# ADC_Board_TOP.net
KiCad netlist of a schematic drawn in Altium Designer
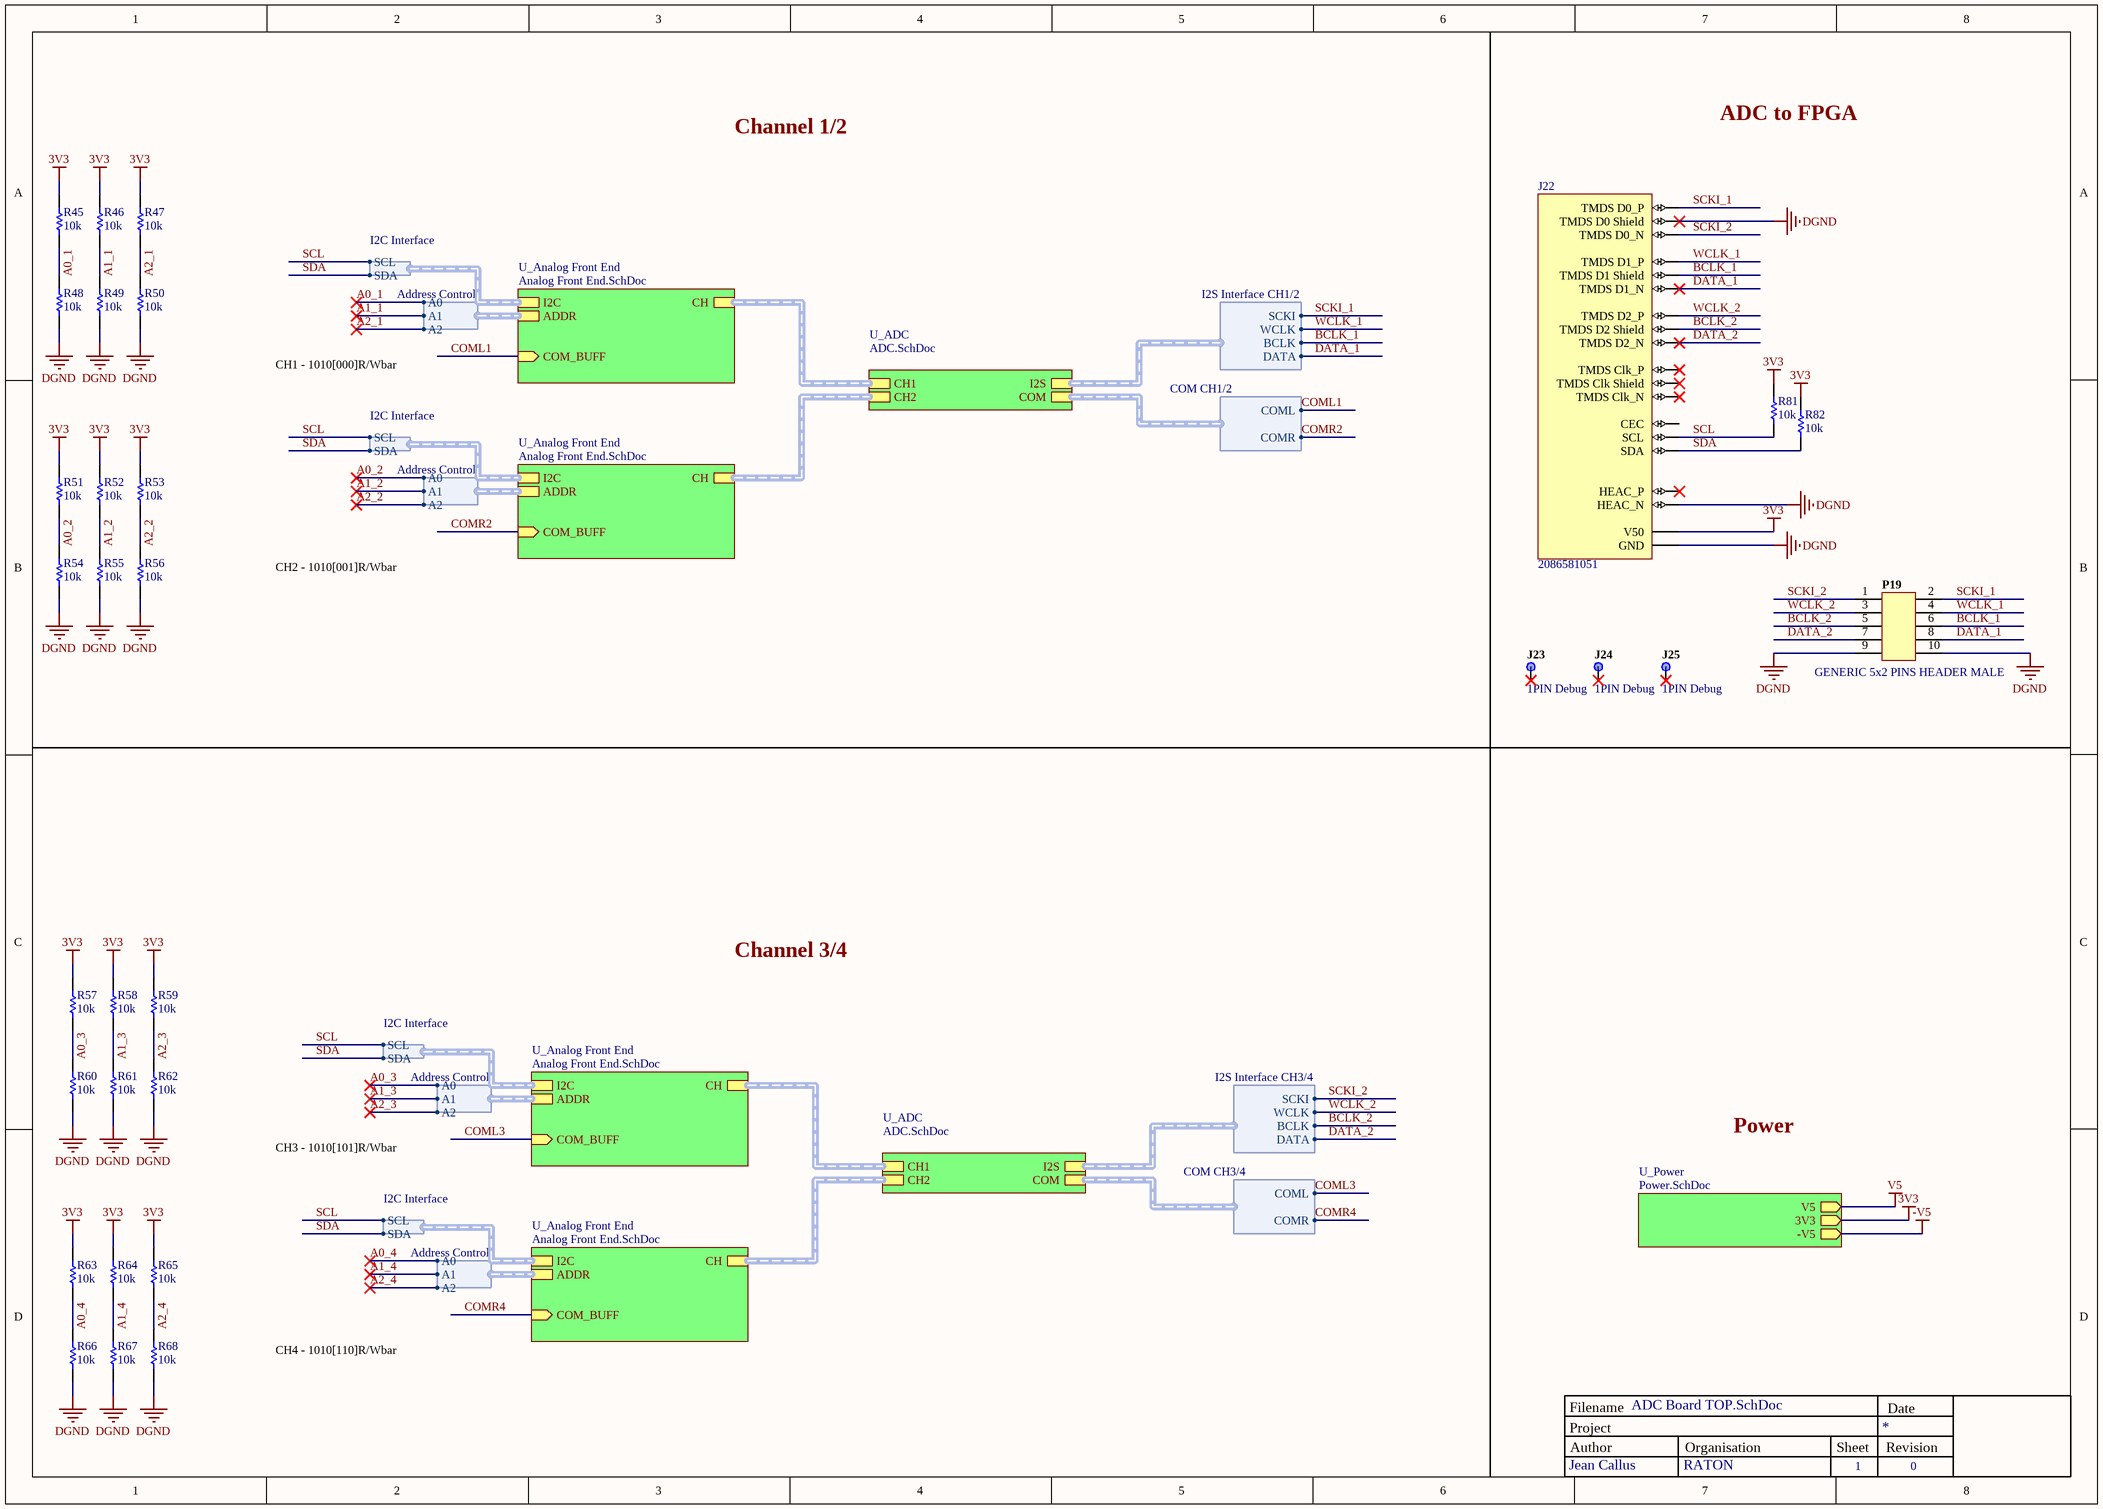
[diagram p0: ADC Board TOP.SchDoc]

(export (version "E")
  (design (tool "Eeschema 10.0.6"))
  (components
    (comp (ref "J22")
      (value "2086581051")
      (footprint "2086581051")
      (description "CONN FEM SMD 19 90Deg HDMI")
      (fields (field (name "DESIGN ITEM ID") "2086581051") (field (name "MANUFACTURER") "Molex"))
      (libsource (lib "") (part "Symbol_1"))
    )
    (comp (ref "J23")
      (value "1PIN Debug")
      (footprint "1 Pin Debug Port 0.9mm")
      (description "CONN MAL TH 1 0Deg HEADER")
      (fields (field (name "DESIGN ITEM ID") "1PIN Debug"))
      (libsource (lib "University of Malta - MEMENTO") (part "1PIN Debug"))
    )
    (comp (ref "J24")
      (value "1PIN Debug")
      (footprint "1 Pin Debug Port 0.9mm")
      (description "CONN MAL TH 1 0Deg HEADER")
      (fields (field (name "DESIGN ITEM ID") "1PIN Debug"))
      (libsource (lib "University of Malta - MEMENTO") (part "1PIN Debug"))
    )
    (comp (ref "J25")
      (value "1PIN Debug")
      (footprint "1 Pin Debug Port 0.9mm")
      (description "CONN MAL TH 1 0Deg HEADER")
      (fields (field (name "DESIGN ITEM ID") "1PIN Debug"))
      (libsource (lib "University of Malta - MEMENTO") (part "1PIN Debug"))
    )
    (comp (ref "P19")
      (value "GENERIC 5x2 PINS HEADER MALE")
      (footprint "GENERIC 5PIN 2ROW HEADER 0")
      (description "CONN MAL TH 5x2 0Deg HEADER")
      (fields
        (field (name "DESIGN ITEM ID") "GENERIC 5x2 PINS HEADER MALE")
        (field (name "MANUFACTURER") "Generic")
      )
      (libsource (lib "University of Malta - MEMENTO") (part "GENERIC 5x2 PINS HEADER MALE"))
    )
    (comp (ref "R45")
      (value "10k")
      (footprint "0402-M")
      (description "RES-10k-0402-63mW-5%")
      (fields (field (name "MANUFACTURER") "Generic") (field (name "Comment") "RES 10k 0402 63mW 5%"))
      (libsource (lib "University of Malta - MEMENTO") (part "Symbol"))
    )
    (comp (ref "R46")
      (value "10k")
      (footprint "0402-M")
      (description "RES-10k-0402-63mW-5%")
      (fields (field (name "MANUFACTURER") "Generic") (field (name "Comment") "RES 10k 0402 63mW 5%"))
      (libsource (lib "University of Malta - MEMENTO") (part "Symbol"))
    )
    (comp (ref "R47")
      (value "10k")
      (footprint "0402-M")
      (description "RES-10k-0402-63mW-5%")
      (fields (field (name "MANUFACTURER") "Generic") (field (name "Comment") "RES 10k 0402 63mW 5%"))
      (libsource (lib "University of Malta - MEMENTO") (part "Symbol"))
    )
    (comp (ref "R48")
      (value "10k")
      (footprint "0402-M")
      (description "RES-10k-0402-63mW-5%")
      (fields (field (name "MANUFACTURER") "Generic") (field (name "Comment") "RES 10k 0402 63mW 5%"))
      (libsource (lib "University of Malta - MEMENTO") (part "Symbol"))
    )
    (comp (ref "R49")
      (value "10k")
      (footprint "0402-M")
      (description "RES-10k-0402-63mW-5%")
      (fields (field (name "MANUFACTURER") "Generic") (field (name "Comment") "RES 10k 0402 63mW 5%"))
      (libsource (lib "University of Malta - MEMENTO") (part "Symbol"))
    )
    (comp (ref "R50")
      (value "10k")
      (footprint "0402-M")
      (description "RES-10k-0402-63mW-5%")
      (fields (field (name "MANUFACTURER") "Generic") (field (name "Comment") "RES 10k 0402 63mW 5%"))
      (libsource (lib "University of Malta - MEMENTO") (part "Symbol"))
    )
    (comp (ref "R51")
      (value "10k")
      (footprint "0402-M")
      (description "RES-10k-0402-63mW-5%")
      (fields (field (name "MANUFACTURER") "Generic") (field (name "Comment") "RES 10k 0402 63mW 5%"))
      (libsource (lib "University of Malta - MEMENTO") (part "Symbol"))
    )
    (comp (ref "R52")
      (value "10k")
      (footprint "0402-M")
      (description "RES-10k-0402-63mW-5%")
      (fields (field (name "MANUFACTURER") "Generic") (field (name "Comment") "RES 10k 0402 63mW 5%"))
      (libsource (lib "University of Malta - MEMENTO") (part "Symbol"))
    )
    (comp (ref "R53")
      (value "10k")
      (footprint "0402-M")
      (description "RES-10k-0402-63mW-5%")
      (fields (field (name "MANUFACTURER") "Generic") (field (name "Comment") "RES 10k 0402 63mW 5%"))
      (libsource (lib "University of Malta - MEMENTO") (part "Symbol"))
    )
    (comp (ref "R54")
      (value "10k")
      (footprint "0402-M")
      (description "RES-10k-0402-63mW-5%")
      (fields (field (name "MANUFACTURER") "Generic") (field (name "Comment") "RES 10k 0402 63mW 5%"))
      (libsource (lib "University of Malta - MEMENTO") (part "Symbol"))
    )
    (comp (ref "R55")
      (value "10k")
      (footprint "0402-M")
      (description "RES-10k-0402-63mW-5%")
      (fields (field (name "MANUFACTURER") "Generic") (field (name "Comment") "RES 10k 0402 63mW 5%"))
      (libsource (lib "University of Malta - MEMENTO") (part "Symbol"))
    )
    (comp (ref "R56")
      (value "10k")
      (footprint "0402-M")
      (description "RES-10k-0402-63mW-5%")
      (fields (field (name "MANUFACTURER") "Generic") (field (name "Comment") "RES 10k 0402 63mW 5%"))
      (libsource (lib "University of Malta - MEMENTO") (part "Symbol"))
    )
    (comp (ref "R57")
      (value "10k")
      (footprint "0402-M")
      (description "RES-10k-0402-63mW-5%")
      (fields (field (name "MANUFACTURER") "Generic") (field (name "Comment") "RES 10k 0402 63mW 5%"))
      (libsource (lib "University of Malta - MEMENTO") (part "Symbol"))
    )
    (comp (ref "R58")
      (value "10k")
      (footprint "0402-M")
      (description "RES-10k-0402-63mW-5%")
      (fields (field (name "MANUFACTURER") "Generic") (field (name "Comment") "RES 10k 0402 63mW 5%"))
      (libsource (lib "University of Malta - MEMENTO") (part "Symbol"))
    )
    (comp (ref "R59")
      (value "10k")
      (footprint "0402-M")
      (description "RES-10k-0402-63mW-5%")
      (fields (field (name "MANUFACTURER") "Generic") (field (name "Comment") "RES 10k 0402 63mW 5%"))
      (libsource (lib "University of Malta - MEMENTO") (part "Symbol"))
    )
    (comp (ref "R60")
      (value "10k")
      (footprint "0402-M")
      (description "RES-10k-0402-63mW-5%")
      (fields (field (name "MANUFACTURER") "Generic") (field (name "Comment") "RES 10k 0402 63mW 5%"))
      (libsource (lib "University of Malta - MEMENTO") (part "Symbol"))
    )
    (comp (ref "R61")
      (value "10k")
      (footprint "0402-M")
      (description "RES-10k-0402-63mW-5%")
      (fields (field (name "MANUFACTURER") "Generic") (field (name "Comment") "RES 10k 0402 63mW 5%"))
      (libsource (lib "University of Malta - MEMENTO") (part "Symbol"))
    )
    (comp (ref "R62")
      (value "10k")
      (footprint "0402-M")
      (description "RES-10k-0402-63mW-5%")
      (fields (field (name "MANUFACTURER") "Generic") (field (name "Comment") "RES 10k 0402 63mW 5%"))
      (libsource (lib "University of Malta - MEMENTO") (part "Symbol"))
    )
    (comp (ref "R63")
      (value "10k")
      (footprint "0402-M")
      (description "RES-10k-0402-63mW-5%")
      (fields (field (name "MANUFACTURER") "Generic") (field (name "Comment") "RES 10k 0402 63mW 5%"))
      (libsource (lib "University of Malta - MEMENTO") (part "Symbol"))
    )
    (comp (ref "R64")
      (value "10k")
      (footprint "0402-M")
      (description "RES-10k-0402-63mW-5%")
      (fields (field (name "MANUFACTURER") "Generic") (field (name "Comment") "RES 10k 0402 63mW 5%"))
      (libsource (lib "University of Malta - MEMENTO") (part "Symbol"))
    )
    (comp (ref "R65")
      (value "10k")
      (footprint "0402-M")
      (description "RES-10k-0402-63mW-5%")
      (fields (field (name "MANUFACTURER") "Generic") (field (name "Comment") "RES 10k 0402 63mW 5%"))
      (libsource (lib "University of Malta - MEMENTO") (part "Symbol"))
    )
    (comp (ref "R66")
      (value "10k")
      (footprint "0402-M")
      (description "RES-10k-0402-63mW-5%")
      (fields (field (name "MANUFACTURER") "Generic") (field (name "Comment") "RES 10k 0402 63mW 5%"))
      (libsource (lib "University of Malta - MEMENTO") (part "Symbol"))
    )
    (comp (ref "R67")
      (value "10k")
      (footprint "0402-M")
      (description "RES-10k-0402-63mW-5%")
      (fields (field (name "MANUFACTURER") "Generic") (field (name "Comment") "RES 10k 0402 63mW 5%"))
      (libsource (lib "University of Malta - MEMENTO") (part "Symbol"))
    )
    (comp (ref "R68")
      (value "10k")
      (footprint "0402-M")
      (description "RES-10k-0402-63mW-5%")
      (fields (field (name "MANUFACTURER") "Generic") (field (name "Comment") "RES 10k 0402 63mW 5%"))
      (libsource (lib "University of Malta - MEMENTO") (part "Symbol"))
    )
    (comp (ref "R81")
      (value "10k")
      (footprint "0402-M")
      (description "RES-10k-0402-63mW-5%")
      (fields (field (name "MANUFACTURER") "Generic") (field (name "Comment") "RES 10k 0402 63mW 5%"))
      (libsource (lib "University of Malta - MEMENTO") (part "Symbol"))
    )
    (comp (ref "R82")
      (value "10k")
      (footprint "0402-M")
      (description "RES-10k-0402-63mW-5%")
      (fields (field (name "MANUFACTURER") "Generic") (field (name "Comment") "RES 10k 0402 63mW 5%"))
      (libsource (lib "University of Malta - MEMENTO") (part "Symbol"))
    )
  )
  (nets
    (net (code "10") (name "/A0_1") (class "Default")
      (node (ref "R45") (pin "1") (pinfunction "1_1") (pintype "passive"))
      (node (ref "R48") (pin "2") (pinfunction "2_2") (pintype "passive"))
    )
    (net (code "11") (name "/A0_2") (class "Default")
      (node (ref "R51") (pin "1") (pinfunction "1_1") (pintype "passive"))
      (node (ref "R54") (pin "2") (pinfunction "2_2") (pintype "passive"))
    )
    (net (code "12") (name "/A0_3") (class "Default")
      (node (ref "R57") (pin "1") (pinfunction "1_1") (pintype "passive"))
      (node (ref "R60") (pin "2") (pinfunction "2_2") (pintype "passive"))
    )
    (net (code "13") (name "/A0_4") (class "Default")
      (node (ref "R63") (pin "1") (pinfunction "1_1") (pintype "passive"))
      (node (ref "R66") (pin "2") (pinfunction "2_2") (pintype "passive"))
    )
    (net (code "14") (name "/A1_1") (class "Default")
      (node (ref "R46") (pin "1") (pinfunction "1_1") (pintype "passive"))
      (node (ref "R49") (pin "2") (pinfunction "2_2") (pintype "passive"))
    )
    (net (code "15") (name "/A1_2") (class "Default")
      (node (ref "R52") (pin "1") (pinfunction "1_1") (pintype "passive"))
      (node (ref "R55") (pin "2") (pinfunction "2_2") (pintype "passive"))
    )
    (net (code "16") (name "/A1_3") (class "Default")
      (node (ref "R58") (pin "1") (pinfunction "1_1") (pintype "passive"))
      (node (ref "R61") (pin "2") (pinfunction "2_2") (pintype "passive"))
    )
    (net (code "17") (name "/A1_4") (class "Default")
      (node (ref "R64") (pin "1") (pinfunction "1_1") (pintype "passive"))
      (node (ref "R67") (pin "2") (pinfunction "2_2") (pintype "passive"))
    )
    (net (code "18") (name "/A2_1") (class "Default")
      (node (ref "R47") (pin "1") (pinfunction "1_1") (pintype "passive"))
      (node (ref "R50") (pin "2") (pinfunction "2_2") (pintype "passive"))
    )
    (net (code "19") (name "/A2_2") (class "Default")
      (node (ref "R53") (pin "1") (pinfunction "1_1") (pintype "passive"))
      (node (ref "R56") (pin "2") (pinfunction "2_2") (pintype "passive"))
    )
    (net (code "20") (name "/A2_3") (class "Default")
      (node (ref "R59") (pin "1") (pinfunction "1_1") (pintype "passive"))
      (node (ref "R62") (pin "2") (pinfunction "2_2") (pintype "passive"))
    )
    (net (code "21") (name "/A2_4") (class "Default")
      (node (ref "R65") (pin "1") (pinfunction "1_1") (pintype "passive"))
      (node (ref "R68") (pin "2") (pinfunction "2_2") (pintype "passive"))
    )
    (net (code "22") (name "/BCLK_1") (class "Default")
      (node (ref "J22") (pin "5") (pinfunction "TMDS_D1_Shield_5") (pintype "bidirectional"))
      (node (ref "P19") (pin "6") (pinfunction "6_6") (pintype "passive"))
    )
    (net (code "23") (name "/BCLK_2") (class "Default")
      (node (ref "J22") (pin "2") (pinfunction "TMDS_D2_Shield_2") (pintype "bidirectional"))
      (node (ref "P19") (pin "5") (pinfunction "5_5") (pintype "passive"))
    )
    (net (code "32") (name "/DATA_1") (class "Default")
      (node (ref "J22") (pin "6") (pinfunction "TMDS_D1_N_6") (pintype "bidirectional"))
      (node (ref "P19") (pin "8") (pinfunction "8_8") (pintype "passive"))
    )
    (net (code "33") (name "/DATA_2") (class "Default")
      (node (ref "J22") (pin "3") (pinfunction "TMDS_D2_N_3") (pintype "bidirectional"))
      (node (ref "P19") (pin "7") (pinfunction "7_7") (pintype "passive"))
    )
    (net (code "34") (name "/SCKI_1") (class "Default")
      (node (ref "J22") (pin "7") (pinfunction "TMDS_D0_P_7") (pintype "bidirectional"))
      (node (ref "P19") (pin "2") (pinfunction "2_2") (pintype "passive"))
    )
    (net (code "35") (name "/SCKI_2") (class "Default")
      (node (ref "J22") (pin "9") (pinfunction "TMDS_D0_N_9") (pintype "bidirectional"))
      (node (ref "P19") (pin "1") (pinfunction "1_1") (pintype "passive"))
    )
    (net (code "36") (name "/SCL") (class "Default")
      (node (ref "J22") (pin "15") (pinfunction "SCL_15") (pintype "bidirectional"))
      (node (ref "R81") (pin "1") (pinfunction "1_1") (pintype "passive"))
    )
    (net (code "37") (name "/SDA") (class "Default")
      (node (ref "J22") (pin "16") (pinfunction "SDA_16") (pintype "bidirectional"))
      (node (ref "R82") (pin "1") (pinfunction "1_1") (pintype "passive"))
    )
    (net (code "38") (name "/WCLK_1") (class "Default")
      (node (ref "J22") (pin "4") (pinfunction "TMDS_D1_P_4") (pintype "bidirectional"))
      (node (ref "P19") (pin "4") (pinfunction "4_4") (pintype "passive"))
    )
    (net (code "39") (name "/WCLK_2") (class "Default")
      (node (ref "J22") (pin "1") (pinfunction "TMDS_D2_P_1") (pintype "bidirectional"))
      (node (ref "P19") (pin "3") (pinfunction "3_3") (pintype "passive"))
    )
    (net (code "46") (name "3V3") (class "Default")
      (node (ref "J22") (pin "18") (pinfunction "V50_18") (pintype "power_in"))
      (node (ref "R45") (pin "2") (pinfunction "2_2") (pintype "passive"))
      (node (ref "R46") (pin "2") (pinfunction "2_2") (pintype "passive"))
      (node (ref "R47") (pin "2") (pinfunction "2_2") (pintype "passive"))
      (node (ref "R51") (pin "2") (pinfunction "2_2") (pintype "passive"))
      (node (ref "R52") (pin "2") (pinfunction "2_2") (pintype "passive"))
      (node (ref "R53") (pin "2") (pinfunction "2_2") (pintype "passive"))
      (node (ref "R57") (pin "2") (pinfunction "2_2") (pintype "passive"))
      (node (ref "R58") (pin "2") (pinfunction "2_2") (pintype "passive"))
      (node (ref "R59") (pin "2") (pinfunction "2_2") (pintype "passive"))
      (node (ref "R63") (pin "2") (pinfunction "2_2") (pintype "passive"))
      (node (ref "R64") (pin "2") (pinfunction "2_2") (pintype "passive"))
      (node (ref "R65") (pin "2") (pinfunction "2_2") (pintype "passive"))
      (node (ref "R81") (pin "2") (pinfunction "2_2") (pintype "passive"))
      (node (ref "R82") (pin "2") (pinfunction "2_2") (pintype "passive"))
    )
    (net (code "47") (name "DGND") (class "Default")
      (node (ref "J22") (pin "17") (pinfunction "GND_17") (pintype "power_in"))
      (node (ref "J22") (pin "19") (pinfunction "HEAC_N_19") (pintype "bidirectional"))
      (node (ref "J22") (pin "8") (pinfunction "TMDS_D0_Shield_8") (pintype "bidirectional"))
      (node (ref "P19") (pin "10") (pinfunction "10_10") (pintype "passive"))
      (node (ref "P19") (pin "9") (pinfunction "9_9") (pintype "passive"))
      (node (ref "R48") (pin "1") (pinfunction "1_1") (pintype "passive"))
      (node (ref "R49") (pin "1") (pinfunction "1_1") (pintype "passive"))
      (node (ref "R50") (pin "1") (pinfunction "1_1") (pintype "passive"))
      (node (ref "R54") (pin "1") (pinfunction "1_1") (pintype "passive"))
      (node (ref "R55") (pin "1") (pinfunction "1_1") (pintype "passive"))
      (node (ref "R56") (pin "1") (pinfunction "1_1") (pintype "passive"))
      (node (ref "R60") (pin "1") (pinfunction "1_1") (pintype "passive"))
      (node (ref "R61") (pin "1") (pinfunction "1_1") (pintype "passive"))
      (node (ref "R62") (pin "1") (pinfunction "1_1") (pintype "passive"))
      (node (ref "R66") (pin "1") (pinfunction "1_1") (pintype "passive"))
      (node (ref "R67") (pin "1") (pinfunction "1_1") (pintype "passive"))
      (node (ref "R68") (pin "1") (pinfunction "1_1") (pintype "passive"))
    )
    (net (code "49") (name "unconnected-(J22-CEC-Pad13)") (class "Default")
      (node (ref "J22") (pin "13") (pinfunction "CEC_13") (pintype "bidirectional"))
    )
    (net (code "50") (name "unconnected-(J22-HEAC_P-Pad14)") (class "Default")
      (node (ref "J22") (pin "14") (pinfunction "HEAC_P_14") (pintype "bidirectional+no_connect"))
    )
    (net (code "51") (name "unconnected-(J22-TMDS_Clk_N-Pad12)") (class "Default")
      (node (ref "J22") (pin "12") (pinfunction "TMDS_Clk_N_12") (pintype "bidirectional+no_connect"))
    )
    (net (code "52") (name "unconnected-(J22-TMDS_Clk_P-Pad10)") (class "Default")
      (node (ref "J22") (pin "10") (pinfunction "TMDS_Clk_P_10") (pintype "bidirectional+no_connect"))
    )
    (net (code "53") (name "unconnected-(J22-TMDS_Clk_Shield-Pad11)") (class "Default")
      (node (ref "J22") (pin "11") (pinfunction "TMDS_Clk_Shield_11") (pintype "bidirectional+no_connect"))
    )
    (net (code "54") (name "unconnected-(J23-Pad1)") (class "Default")
      (node (ref "J23") (pin "1") (pinfunction "1_1") (pintype "passive+no_connect"))
    )
    (net (code "55") (name "unconnected-(J24-Pad1)") (class "Default")
      (node (ref "J24") (pin "1") (pinfunction "1_1") (pintype "passive+no_connect"))
    )
    (net (code "56") (name "unconnected-(J25-Pad1)") (class "Default")
      (node (ref "J25") (pin "1") (pinfunction "1_1") (pintype "passive+no_connect"))
    )
  )
)
